# p4_joint.net
KiCad netlist of a schematic drawn in EAGLE
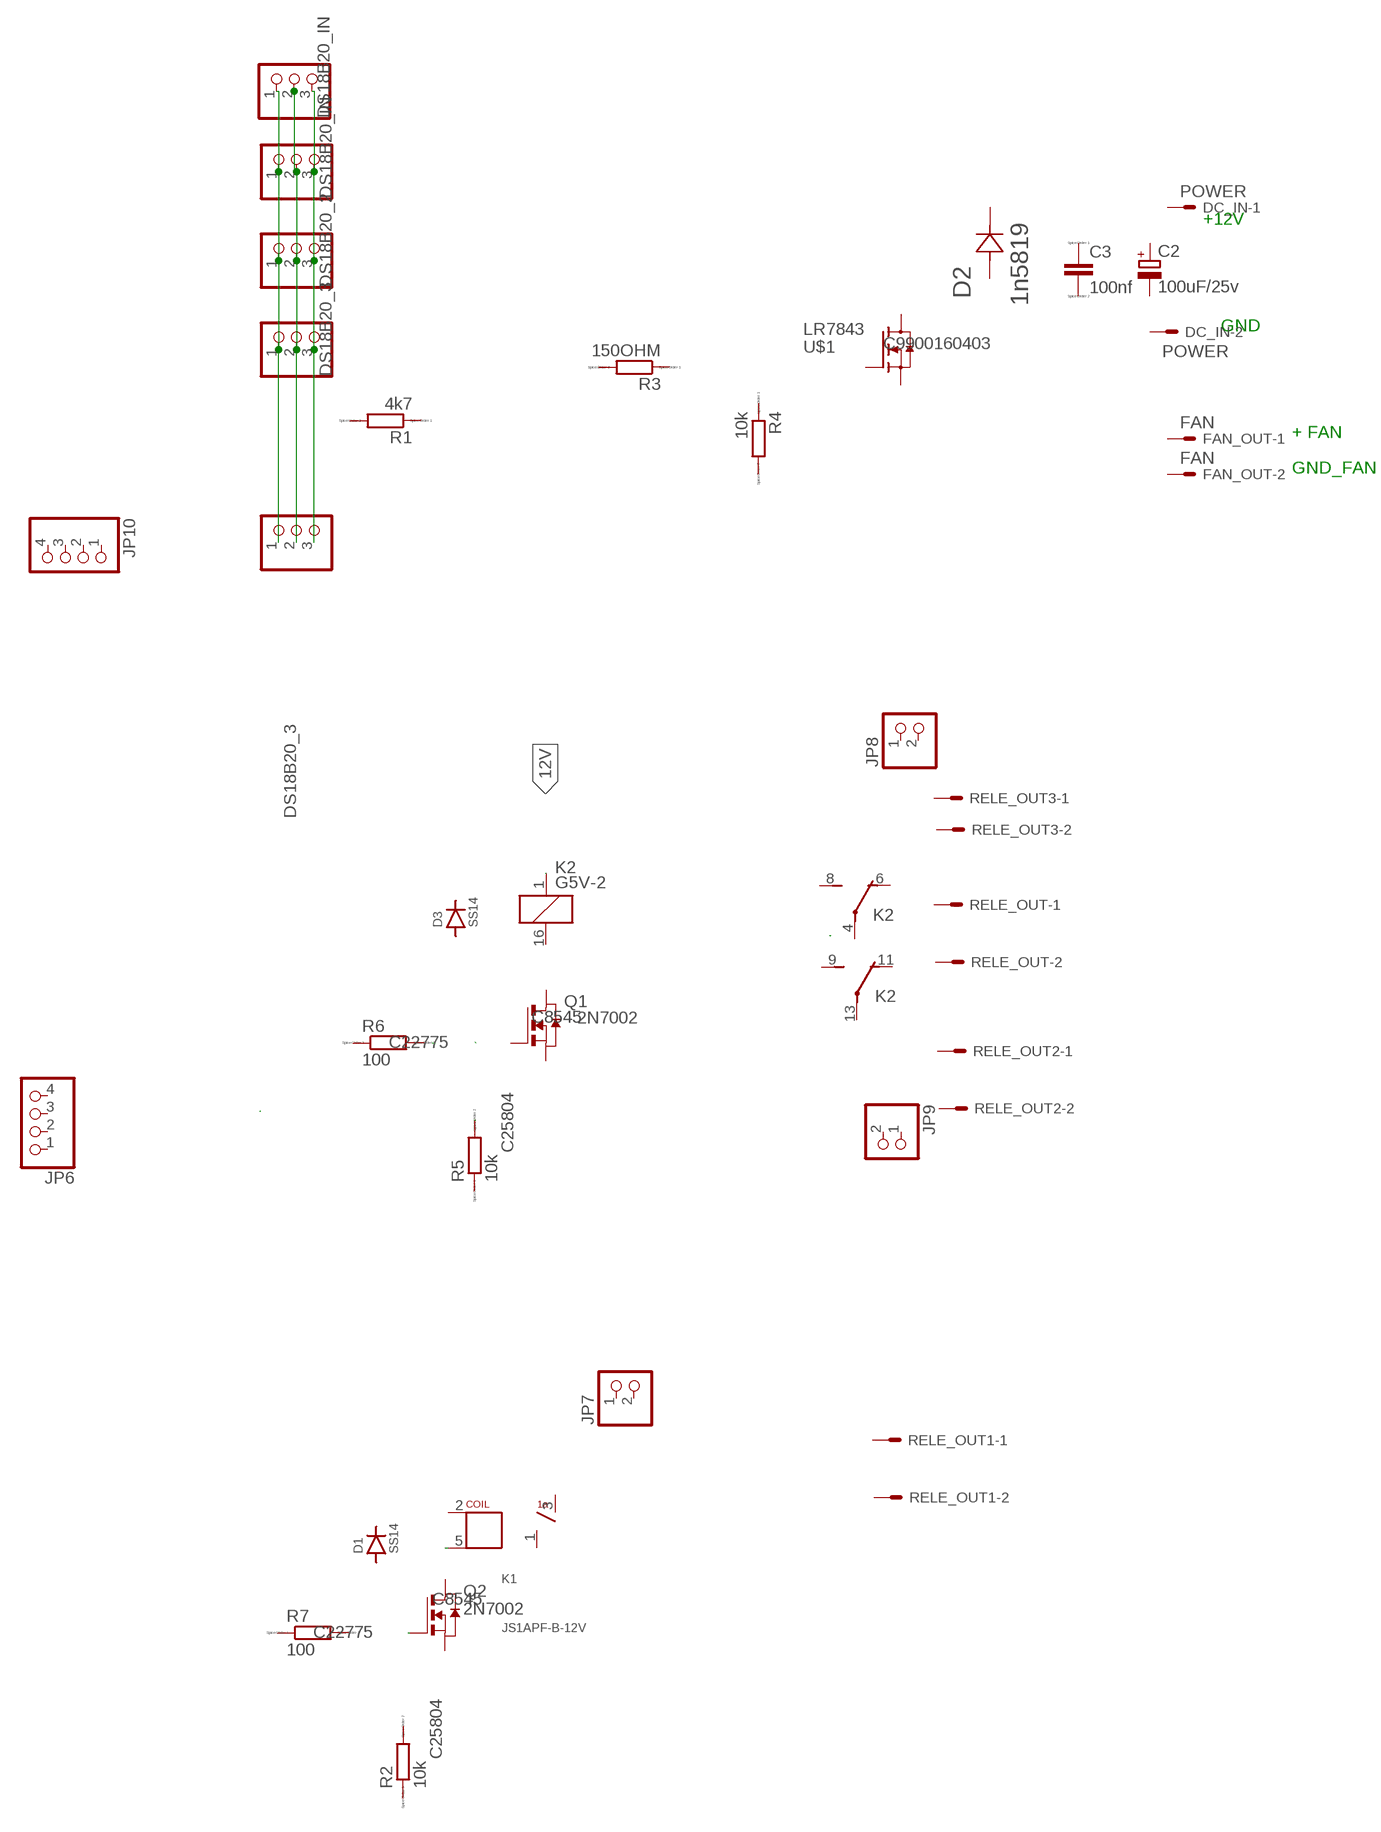
[diagram p0: schematic, sheet 1]

(export (version "E")
  (design (tool "Eeschema 10.0.6"))
  (components
    (comp (ref "C2")
      (value "100uF/25v")
      (footprint "eagle-import:PANASONIC_C")
      (libsource (lib "eagle-import") (part "CPOL-EUC"))
    )
    (comp (ref "C3")
      (value "100nf")
      (footprint "eagle-import:C0603")
      (libsource (lib "eagle-import") (part "CC0603"))
    )
    (comp (ref "D1")
      (value "SS14")
      (footprint "eagle-import:SMA")
      (libsource (lib "eagle-import") (part "SS14"))
    )
    (comp (ref "D2")
      (value "1n5819")
      (footprint "eagle-import:SOD123-M")
      (fields
        (field (name "MANUFACTURER_PART_NUMBER") "1N4148W7F")
        (field (name "COPYRIGHT") "Copyright C 2015 Accelerated Designs. All rights reserved")
      )
      (libsource (lib "eagle-import") (part "1N4148W-7-FSOD123-M"))
    )
    (comp (ref "D3")
      (value "SS14")
      (footprint "eagle-import:SMA")
      (libsource (lib "eagle-import") (part "SS14"))
    )
    (comp (ref "DC_IN")
      (value "POWER")
      (footprint "eagle-import:KK-156-2")
      (fields (field (name "MF") "MOLEX"))
      (libsource (lib "eagle-import") (part "KK-156-2"))
    )
    (comp (ref "FAN_OUT")
      (value "FAN")
      (footprint "eagle-import:KK-156-2")
      (fields (field (name "MF") "MOLEX"))
      (libsource (lib "eagle-import") (part "KK-156-2"))
    )
    (comp (ref "JP1")
      (value "DS18B20_IN")
      (footprint "eagle-import:1X03")
      (libsource (lib "eagle-import") (part "PINHD-1X3"))
    )
    (comp (ref "JP2")
      (value "DS18B20_IN")
      (footprint "eagle-import:1X03")
      (libsource (lib "eagle-import") (part "PINHD-1X3"))
    )
    (comp (ref "JP3")
      (value "DS18B20_3")
      (footprint "eagle-import:1X03")
      (libsource (lib "eagle-import") (part "PINHD-1X3"))
    )
    (comp (ref "JP4")
      (value "DS18B20_2")
      (footprint "eagle-import:1X03")
      (libsource (lib "eagle-import") (part "PINHD-1X3"))
    )
    (comp (ref "JP5")
      (value "DS18B20_3")
      (footprint "eagle-import:1X03")
      (libsource (lib "eagle-import") (part "PINHD-1X3"))
    )
    (comp (ref "JP6")
      (value "PINHD-1X4")
      (footprint "eagle-import:1X04")
      (libsource (lib "eagle-import") (part "PINHD-1X4"))
    )
    (comp (ref "JP7")
      (value "PINHD-1X2")
      (footprint "eagle-import:1X02")
      (libsource (lib "eagle-import") (part "PINHD-1X2"))
    )
    (comp (ref "JP8")
      (value "PINHD-1X2")
      (footprint "eagle-import:1X02")
      (libsource (lib "eagle-import") (part "PINHD-1X2"))
    )
    (comp (ref "JP9")
      (value "PINHD-1X2")
      (footprint "eagle-import:1X02")
      (libsource (lib "eagle-import") (part "PINHD-1X2"))
    )
    (comp (ref "JP10")
      (value "PINHD-1X4")
      (footprint "eagle-import:1X04")
      (libsource (lib "eagle-import") (part "PINHD-1X4"))
    )
    (comp (ref "K1")
      (value "JS1APF-B-12V")
      (footprint "eagle-import:JS_RELAY_1A")
      (libsource (lib "eagle-import") (part "JS1APF-B-12V"))
    )
    (comp (ref "K2")
      (value "G5V-2")
      (footprint "eagle-import:G5V-2")
      (fields (field (name "MPN") "G5V-2 5DC"))
      (libsource (lib "eagle-import") (part "G5V-2"))
    )
    (comp (ref "Q1")
      (value "2N7002")
      (footprint "eagle-import:SOT-23")
      (fields (field (name "LCSC") "C8545"))
      (libsource (lib "eagle-import") (part "NMOSSOT23"))
    )
    (comp (ref "Q2")
      (value "2N7002")
      (footprint "eagle-import:SOT-23")
      (fields (field (name "LCSC") "C8545"))
      (libsource (lib "eagle-import") (part "NMOSSOT23"))
    )
    (comp (ref "R1")
      (value "4k7")
      (footprint "eagle-import:R0603")
      (libsource (lib "eagle-import") (part "RR0603"))
    )
    (comp (ref "R2")
      (value "10k")
      (footprint "eagle-import:R0805")
      (fields (field (name "LCSC") "C25804"))
      (libsource (lib "eagle-import") (part "R"))
    )
    (comp (ref "R3")
      (value "150OHM")
      (footprint "eagle-import:R0603")
      (libsource (lib "eagle-import") (part "RR0603"))
    )
    (comp (ref "R4")
      (value "10k")
      (footprint "eagle-import:R0603")
      (libsource (lib "eagle-import") (part "RR0603"))
    )
    (comp (ref "R5")
      (value "10k")
      (footprint "eagle-import:R0805")
      (fields (field (name "LCSC") "C25804"))
      (libsource (lib "eagle-import") (part "R"))
    )
    (comp (ref "R6")
      (value "100")
      (footprint "eagle-import:R0805")
      (fields (field (name "LCSC") "C22775"))
      (libsource (lib "eagle-import") (part "R"))
    )
    (comp (ref "R7")
      (value "100")
      (footprint "eagle-import:R0805")
      (fields (field (name "LCSC") "C22775"))
      (libsource (lib "eagle-import") (part "R"))
    )
    (comp (ref "RELE_OUT")
      (value "KK-156-2")
      (footprint "eagle-import:KK-156-2")
      (fields (field (name "MF") "MOLEX"))
      (libsource (lib "eagle-import") (part "KK-156-2"))
    )
    (comp (ref "RELE_OUT1")
      (value "KK-156-2")
      (footprint "eagle-import:KK-156-2")
      (fields (field (name "MF") "MOLEX"))
      (libsource (lib "eagle-import") (part "KK-156-2"))
    )
    (comp (ref "RELE_OUT2")
      (value "KK-156-2")
      (footprint "eagle-import:KK-156-2")
      (fields (field (name "MF") "MOLEX"))
      (libsource (lib "eagle-import") (part "KK-156-2"))
    )
    (comp (ref "RELE_OUT3")
      (value "KK-156-2")
      (footprint "eagle-import:KK-156-2")
      (fields (field (name "MF") "MOLEX"))
      (libsource (lib "eagle-import") (part "KK-156-2"))
    )
    (comp (ref "U$1")
      (value "LR7843")
      (footprint "eagle-import:TO252")
      (fields (field (name "LCSC") "C9900160403"))
      (libsource (lib "eagle-import") (part "IRLR7843"))
    )
  )
  (nets
    (net (code "1") (name "12V") (class "Default")
      (node (ref "K2") (pin "1") (pinfunction "1_1") (pintype "passive"))
    )
    (net (code "2") (name "Net-(JP1-Pad1)") (class "Default")
      (node (ref "JP1") (pin "1") (pinfunction "1_1") (pintype "passive"))
      (node (ref "JP2") (pin "1") (pinfunction "1_1") (pintype "passive"))
      (node (ref "JP3") (pin "1") (pinfunction "1_1") (pintype "passive"))
      (node (ref "JP4") (pin "1") (pinfunction "1_1") (pintype "passive"))
      (node (ref "JP5") (pin "1") (pinfunction "1_1") (pintype "passive"))
    )
    (net (code "3") (name "Net-(JP1-Pad2)") (class "Default")
      (node (ref "JP1") (pin "2") (pinfunction "2_2") (pintype "passive"))
      (node (ref "JP2") (pin "2") (pinfunction "2_2") (pintype "passive"))
      (node (ref "JP3") (pin "2") (pinfunction "2_2") (pintype "passive"))
      (node (ref "JP4") (pin "2") (pinfunction "2_2") (pintype "passive"))
      (node (ref "JP5") (pin "2") (pinfunction "2_2") (pintype "passive"))
    )
    (net (code "4") (name "Net-(JP1-Pad3)") (class "Default")
      (node (ref "JP1") (pin "3") (pinfunction "3_3") (pintype "passive"))
      (node (ref "JP2") (pin "3") (pinfunction "3_3") (pintype "passive"))
      (node (ref "JP3") (pin "3") (pinfunction "3_3") (pintype "passive"))
      (node (ref "JP4") (pin "3") (pinfunction "3_3") (pintype "passive"))
      (node (ref "JP5") (pin "3") (pinfunction "3_3") (pintype "passive"))
    )
    (net (code "5") (name "unconnected-(C2-Pad+)") (class "Default")
      (node (ref "C2") (pin "+") (pinfunction "+_+") (pintype "passive"))
    )
    (net (code "6") (name "unconnected-(C2-Pad-)") (class "Default")
      (node (ref "C2") (pin "-") (pinfunction "-_-") (pintype "passive"))
    )
    (net (code "7") (name "unconnected-(C3-Pad1)") (class "Default")
      (node (ref "C3") (pin "1") (pinfunction "1_1") (pintype "passive"))
    )
    (net (code "8") (name "unconnected-(C3-Pad2)") (class "Default")
      (node (ref "C3") (pin "2") (pinfunction "2_2") (pintype "passive"))
    )
    (net (code "9") (name "unconnected-(D1-PadA)") (class "Default")
      (node (ref "D1") (pin "A") (pinfunction "A_A") (pintype "passive"))
    )
    (net (code "10") (name "unconnected-(D1-PadC)") (class "Default")
      (node (ref "D1") (pin "C") (pinfunction "C_C") (pintype "passive"))
    )
    (net (code "11") (name "unconnected-(D2-12-PadC)") (class "Default")
      (node (ref "D2") (pin "C") (pinfunction "12_C") (pintype "passive"))
    )
    (net (code "12") (name "unconnected-(D2-21-PadA)") (class "Default")
      (node (ref "D2") (pin "A") (pinfunction "21_A") (pintype "passive"))
    )
    (net (code "13") (name "unconnected-(D3-PadA)") (class "Default")
      (node (ref "D3") (pin "A") (pinfunction "A_A") (pintype "passive"))
    )
    (net (code "14") (name "unconnected-(D3-PadC)") (class "Default")
      (node (ref "D3") (pin "C") (pinfunction "C_C") (pintype "passive"))
    )
    (net (code "15") (name "unconnected-(DC_INA-S-Pad1)") (class "Default")
      (node (ref "DC_IN") (pin "1") (pinfunction "S_1") (pintype "passive"))
    )
    (net (code "16") (name "unconnected-(DC_INB-S-Pad2)") (class "Default")
      (node (ref "DC_IN") (pin "2") (pinfunction "S_2") (pintype "passive"))
    )
    (net (code "17") (name "unconnected-(FAN_OUTA-S-Pad1)") (class "Default")
      (node (ref "FAN_OUT") (pin "1") (pinfunction "S_1") (pintype "passive"))
    )
    (net (code "18") (name "unconnected-(FAN_OUTB-S-Pad2)") (class "Default")
      (node (ref "FAN_OUT") (pin "2") (pinfunction "S_2") (pintype "passive"))
    )
    (net (code "19") (name "unconnected-(JP6-Pad1)") (class "Default")
      (node (ref "JP6") (pin "1") (pinfunction "1_1") (pintype "passive"))
    )
    (net (code "20") (name "unconnected-(JP6-Pad2)") (class "Default")
      (node (ref "JP6") (pin "2") (pinfunction "2_2") (pintype "passive"))
    )
    (net (code "21") (name "unconnected-(JP6-Pad3)") (class "Default")
      (node (ref "JP6") (pin "3") (pinfunction "3_3") (pintype "passive"))
    )
    (net (code "22") (name "unconnected-(JP6-Pad4)") (class "Default")
      (node (ref "JP6") (pin "4") (pinfunction "4_4") (pintype "passive"))
    )
    (net (code "23") (name "unconnected-(JP7-Pad1)") (class "Default")
      (node (ref "JP7") (pin "1") (pinfunction "1_1") (pintype "passive"))
    )
    (net (code "24") (name "unconnected-(JP7-Pad2)") (class "Default")
      (node (ref "JP7") (pin "2") (pinfunction "2_2") (pintype "passive"))
    )
    (net (code "25") (name "unconnected-(JP8-Pad1)") (class "Default")
      (node (ref "JP8") (pin "1") (pinfunction "1_1") (pintype "passive"))
    )
    (net (code "26") (name "unconnected-(JP8-Pad2)") (class "Default")
      (node (ref "JP8") (pin "2") (pinfunction "2_2") (pintype "passive"))
    )
    (net (code "27") (name "unconnected-(JP9-Pad1)") (class "Default")
      (node (ref "JP9") (pin "1") (pinfunction "1_1") (pintype "passive"))
    )
    (net (code "28") (name "unconnected-(JP9-Pad2)") (class "Default")
      (node (ref "JP9") (pin "2") (pinfunction "2_2") (pintype "passive"))
    )
    (net (code "29") (name "unconnected-(JP10-Pad1)") (class "Default")
      (node (ref "JP10") (pin "1") (pinfunction "1_1") (pintype "passive"))
    )
    (net (code "30") (name "unconnected-(JP10-Pad2)") (class "Default")
      (node (ref "JP10") (pin "2") (pinfunction "2_2") (pintype "passive"))
    )
    (net (code "31") (name "unconnected-(JP10-Pad3)") (class "Default")
      (node (ref "JP10") (pin "3") (pinfunction "3_3") (pintype "passive"))
    )
    (net (code "32") (name "unconnected-(JP10-Pad4)") (class "Default")
      (node (ref "JP10") (pin "4") (pinfunction "4_4") (pintype "passive"))
    )
    (net (code "33") (name "unconnected-(K1-C1-Pad2)") (class "Default")
      (node (ref "K1") (pin "2") (pinfunction "C1_2") (pintype "passive"))
    )
    (net (code "34") (name "unconnected-(K1-C2-Pad5)") (class "Default")
      (node (ref "K1") (pin "5") (pinfunction "C2_5") (pintype "passive"))
    )
    (net (code "35") (name "unconnected-(K1-COM-Pad1)") (class "Default")
      (node (ref "K1") (pin "1") (pinfunction "COM_1") (pintype "passive"))
    )
    (net (code "36") (name "unconnected-(K1-NO-Pad3)") (class "Default")
      (node (ref "K1") (pin "3") (pinfunction "NO_3") (pintype "passive"))
    )
    (net (code "37") (name "unconnected-(K2A-O-Pad6)") (class "Default")
      (node (ref "K2") (pin "6") (pinfunction "O_6") (pintype "passive"))
    )
    (net (code "38") (name "unconnected-(K2A-P-Pad4)") (class "Default")
      (node (ref "K2") (pin "4") (pinfunction "P_4") (pintype "passive"))
    )
    (net (code "39") (name "unconnected-(K2A-S-Pad8)") (class "Default")
      (node (ref "K2") (pin "8") (pinfunction "S_8") (pintype "passive"))
    )
    (net (code "40") (name "unconnected-(K2B-O-Pad11)") (class "Default")
      (node (ref "K2") (pin "11") (pinfunction "O_11") (pintype "passive"))
    )
    (net (code "41") (name "unconnected-(K2B-P-Pad13)") (class "Default")
      (node (ref "K2") (pin "13") (pinfunction "P_13") (pintype "passive"))
    )
    (net (code "42") (name "unconnected-(K2B-S-Pad9)") (class "Default")
      (node (ref "K2") (pin "9") (pinfunction "S_9") (pintype "passive"))
    )
    (net (code "43") (name "unconnected-(K2C-2-Pad16)") (class "Default")
      (node (ref "K2") (pin "16") (pinfunction "2_16") (pintype "passive"))
    )
    (net (code "44") (name "unconnected-(Q1-D-Pad1)") (class "Default")
      (node (ref "Q1") (pin "1") (pinfunction "D_1") (pintype "passive"))
    )
    (net (code "45") (name "unconnected-(Q1-G-Pad3)") (class "Default")
      (node (ref "Q1") (pin "3") (pinfunction "G_3") (pintype "passive"))
    )
    (net (code "46") (name "unconnected-(Q1-S-Pad2)") (class "Default")
      (node (ref "Q1") (pin "2") (pinfunction "S_2") (pintype "passive"))
    )
    (net (code "47") (name "unconnected-(Q2-D-Pad1)") (class "Default")
      (node (ref "Q2") (pin "1") (pinfunction "D_1") (pintype "passive"))
    )
    (net (code "48") (name "unconnected-(Q2-G-Pad3)") (class "Default")
      (node (ref "Q2") (pin "3") (pinfunction "G_3") (pintype "passive"))
    )
    (net (code "49") (name "unconnected-(Q2-S-Pad2)") (class "Default")
      (node (ref "Q2") (pin "2") (pinfunction "S_2") (pintype "passive"))
    )
    (net (code "50") (name "unconnected-(R1-Pad1)") (class "Default")
      (node (ref "R1") (pin "1") (pinfunction "1_1") (pintype "passive"))
    )
    (net (code "51") (name "unconnected-(R1-Pad2)") (class "Default")
      (node (ref "R1") (pin "2") (pinfunction "2_2") (pintype "passive"))
    )
    (net (code "52") (name "unconnected-(R2-Pad1)") (class "Default")
      (node (ref "R2") (pin "1") (pinfunction "1_1") (pintype "passive"))
    )
    (net (code "53") (name "unconnected-(R2-Pad2)") (class "Default")
      (node (ref "R2") (pin "2") (pinfunction "2_2") (pintype "passive"))
    )
    (net (code "54") (name "unconnected-(R3-Pad1)") (class "Default")
      (node (ref "R3") (pin "1") (pinfunction "1_1") (pintype "passive"))
    )
    (net (code "55") (name "unconnected-(R3-Pad2)") (class "Default")
      (node (ref "R3") (pin "2") (pinfunction "2_2") (pintype "passive"))
    )
    (net (code "56") (name "unconnected-(R4-Pad1)") (class "Default")
      (node (ref "R4") (pin "1") (pinfunction "1_1") (pintype "passive"))
    )
    (net (code "57") (name "unconnected-(R4-Pad2)") (class "Default")
      (node (ref "R4") (pin "2") (pinfunction "2_2") (pintype "passive"))
    )
    (net (code "58") (name "unconnected-(R5-Pad1)") (class "Default")
      (node (ref "R5") (pin "1") (pinfunction "1_1") (pintype "passive"))
    )
    (net (code "59") (name "unconnected-(R5-Pad2)") (class "Default")
      (node (ref "R5") (pin "2") (pinfunction "2_2") (pintype "passive"))
    )
    (net (code "60") (name "unconnected-(R6-Pad1)") (class "Default")
      (node (ref "R6") (pin "1") (pinfunction "1_1") (pintype "passive"))
    )
    (net (code "61") (name "unconnected-(R6-Pad2)") (class "Default")
      (node (ref "R6") (pin "2") (pinfunction "2_2") (pintype "passive"))
    )
    (net (code "62") (name "unconnected-(R7-Pad1)") (class "Default")
      (node (ref "R7") (pin "1") (pinfunction "1_1") (pintype "passive"))
    )
    (net (code "63") (name "unconnected-(R7-Pad2)") (class "Default")
      (node (ref "R7") (pin "2") (pinfunction "2_2") (pintype "passive"))
    )
    (net (code "64") (name "unconnected-(RELE_OUT1A-S-Pad1)") (class "Default")
      (node (ref "RELE_OUT1") (pin "1") (pinfunction "S_1") (pintype "passive"))
    )
    (net (code "65") (name "unconnected-(RELE_OUT1B-S-Pad2)") (class "Default")
      (node (ref "RELE_OUT1") (pin "2") (pinfunction "S_2") (pintype "passive"))
    )
    (net (code "66") (name "unconnected-(RELE_OUT2A-S-Pad1)") (class "Default")
      (node (ref "RELE_OUT2") (pin "1") (pinfunction "S_1") (pintype "passive"))
    )
    (net (code "67") (name "unconnected-(RELE_OUT2B-S-Pad2)") (class "Default")
      (node (ref "RELE_OUT2") (pin "2") (pinfunction "S_2") (pintype "passive"))
    )
    (net (code "68") (name "unconnected-(RELE_OUT3A-S-Pad1)") (class "Default")
      (node (ref "RELE_OUT3") (pin "1") (pinfunction "S_1") (pintype "passive"))
    )
    (net (code "69") (name "unconnected-(RELE_OUT3B-S-Pad2)") (class "Default")
      (node (ref "RELE_OUT3") (pin "2") (pinfunction "S_2") (pintype "passive"))
    )
    (net (code "70") (name "unconnected-(RELE_OUTA-S-Pad1)") (class "Default")
      (node (ref "RELE_OUT") (pin "1") (pinfunction "S_1") (pintype "passive"))
    )
    (net (code "71") (name "unconnected-(RELE_OUTB-S-Pad2)") (class "Default")
      (node (ref "RELE_OUT") (pin "2") (pinfunction "S_2") (pintype "passive"))
    )
    (net (code "72") (name "unconnected-(U$1-D-Pad3)") (class "Default")
      (node (ref "U$1") (pin "3") (pinfunction "D_3") (pintype "passive"))
    )
    (net (code "73") (name "unconnected-(U$1-G-Pad1)") (class "Default")
      (node (ref "U$1") (pin "1") (pinfunction "G_1") (pintype "passive"))
    )
    (net (code "74") (name "unconnected-(U$1-S-Pad2)") (class "Default")
      (node (ref "U$1") (pin "2") (pinfunction "S_2") (pintype "passive"))
    )
  )
)
